# Power-scheme.net
KiCad netlist of a schematic drawn in Altium Designer
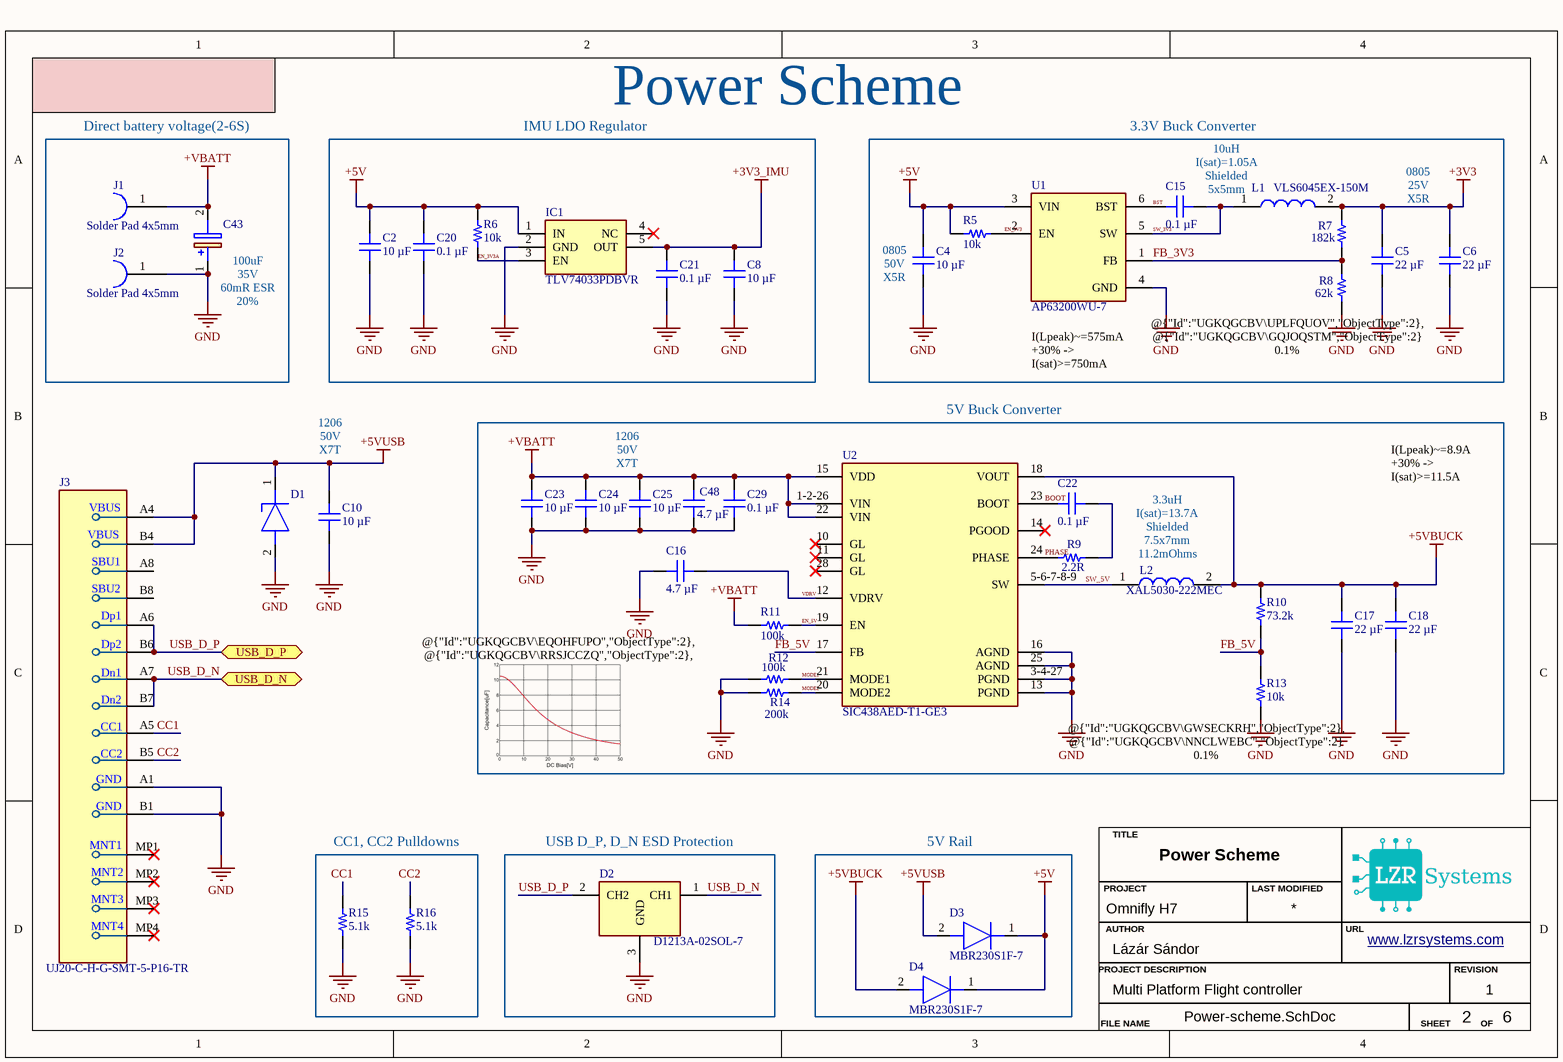
[diagram p0: Power-scheme.SchDoc]

(export (version "E")
  (design (tool "Eeschema 10.0.6"))
  (components
    (comp (ref "C2")
      (value "10 µF")
      (footprint "MURATA GRM21B 0805_2012")
      (description "CAP CER 10UF 50V X5R 0805")
      (fields
        (field (name "PART NUMBER") "GRM21BR61H106ME43L")
        (field (name "CAPACITANCE") "10 µF")
        (field (name "MANUFACTURER") "Murata Electronics")
      )
      (libsource (lib "Celestial Altium Library - altium_library") (part "Capacitor"))
    )
    (comp (ref "C4")
      (value "10 µF")
      (footprint "MURATA GRM21B 0805_2012")
      (description "CAP CER 10UF 50V X5R 0805")
      (fields
        (field (name "PART NUMBER") "GRM21BR61H106ME43L")
        (field (name "CAPACITANCE") "10 µF")
        (field (name "MANUFACTURER") "Murata Electronics")
      )
      (libsource (lib "Celestial Altium Library - altium_library") (part "Capacitor"))
    )
    (comp (ref "C5")
      (value "22 µF")
      (footprint "MURATA GRM21B 0805_2012")
      (description "CAP CER 22UF 16V X5R 0805")
      (fields
        (field (name "PART NUMBER") "GRM21BR61C226ME44L")
        (field (name "CAPACITANCE") "22 µF")
        (field (name "MANUFACTURER") "Murata Electronics")
      )
      (libsource (lib "Celestial Altium Library - altium_library") (part "Capacitor"))
    )
    (comp (ref "C6")
      (value "22 µF")
      (footprint "MURATA GRM21B 0805_2012")
      (description "CAP CER 22UF 16V X5R 0805")
      (fields
        (field (name "PART NUMBER") "GRM21BR61C226ME44L")
        (field (name "CAPACITANCE") "22 µF")
        (field (name "MANUFACTURER") "Murata Electronics")
      )
      (libsource (lib "Celestial Altium Library - altium_library") (part "Capacitor"))
    )
    (comp (ref "C8")
      (value "10 µF")
      (footprint "MURATA GRM21B 0805_2012")
      (description "CAP CER 10UF 50V X5R 0805")
      (fields
        (field (name "PART NUMBER") "GRM21BR61H106ME43L")
        (field (name "CAPACITANCE") "10 µF")
        (field (name "MANUFACTURER") "Murata Electronics")
      )
      (libsource (lib "Celestial Altium Library - altium_library") (part "Capacitor"))
    )
    (comp (ref "C10")
      (value "10 µF")
      (footprint "MURATA GRM21B 0805_2012")
      (description "CAP CER 10UF 50V X5R 0805")
      (fields
        (field (name "PART NUMBER") "GRM21BR61H106ME43L")
        (field (name "CAPACITANCE") "10 µF")
        (field (name "MANUFACTURER") "Murata Electronics")
      )
      (libsource (lib "Celestial Altium Library - altium_library") (part "Capacitor"))
    )
    (comp (ref "C15")
      (value "0.1 µF")
      (footprint "MURATA GCM155 0402_1005")
      (description "CAP CER 0.1UF 50V X7R 0402")
      (fields
        (field (name "PART NUMBER") "GCM155R71H104ME02D")
        (field (name "CAPACITANCE") "0.1 µF")
        (field (name "MANUFACTURER") "Murata Electronics")
      )
      (libsource (lib "Celestial Altium Library - altium_library") (part "Capacitor"))
    )
    (comp (ref "C16")
      (value "4.7 µF")
      (footprint "MURATA GRM21B 0805_2012")
      (description "CAP CER 4.7UF 50V X5R 0805")
      (fields
        (field (name "PART NUMBER") "GRM21BR61H475KE51L")
        (field (name "CAPACITANCE") "4.7 µF")
        (field (name "MANUFACTURER") "Murata Electronics")
      )
      (libsource (lib "Celestial Altium Library - altium_library") (part "Capacitor"))
    )
    (comp (ref "C17")
      (value "22 µF")
      (footprint "CAP 1206_3216 - 0.8MM")
      (description "CAP CER 22UF 16V X6S 1206")
      (fields
        (field (name "PART NUMBER") "GRT31CC81C226ME01L")
        (field (name "CAPACITANCE") "22 µF")
        (field (name "MANUFACTURER") "Murata Electronics")
      )
      (libsource (lib "Celestial Altium Library - altium_library") (part "Capacitor"))
    )
    (comp (ref "C18")
      (value "22 µF")
      (footprint "CAP 1206_3216 - 0.8MM")
      (description "CAP CER 22UF 16V X6S 1206")
      (fields
        (field (name "PART NUMBER") "GRT31CC81C226ME01L")
        (field (name "CAPACITANCE") "22 µF")
        (field (name "MANUFACTURER") "Murata Electronics")
      )
      (libsource (lib "Celestial Altium Library - altium_library") (part "Capacitor"))
    )
    (comp (ref "C20")
      (value "0.1 µF")
      (footprint "MURATA GCM155 0402_1005")
      (description "CAP CER 0.1UF 50V X7R 0402")
      (fields
        (field (name "PART NUMBER") "GCM155R71H104ME02D")
        (field (name "CAPACITANCE") "0.1 µF")
        (field (name "MANUFACTURER") "Murata Electronics")
      )
      (libsource (lib "Celestial Altium Library - altium_library") (part "Capacitor"))
    )
    (comp (ref "C21")
      (value "0.1 µF")
      (footprint "MURATA GCM155 0402_1005")
      (description "CAP CER 0.1UF 50V X7R 0402")
      (fields
        (field (name "PART NUMBER") "GCM155R71H104ME02D")
        (field (name "CAPACITANCE") "0.1 µF")
        (field (name "MANUFACTURER") "Murata Electronics")
      )
      (libsource (lib "Celestial Altium Library - altium_library") (part "Capacitor"))
    )
    (comp (ref "C22")
      (value "0.1 µF")
      (footprint "MURATA GCM155 0402_1005")
      (description "CAP CER 0.1UF 50V X7R 0402")
      (fields
        (field (name "PART NUMBER") "GCM155R71H104ME02D")
        (field (name "CAPACITANCE") "0.1 µF")
        (field (name "MANUFACTURER") "Murata Electronics")
      )
      (libsource (lib "Celestial Altium Library - altium_library") (part "Capacitor"))
    )
    (comp (ref "C23")
      (value "10 µF")
      (footprint "CAP 1206_3216 - 0.8MM")
      (description "CAP CER 10UF 50V X5R 1206")
      (fields
        (field (name "PART NUMBER") "CGA5L3X5R1H106K160AB")
        (field (name "CAPACITANCE") "10 µF")
        (field (name "MANUFACTURER") "TDK Corporation")
      )
      (libsource (lib "Celestial Altium Library - altium_library") (part "Capacitor"))
    )
    (comp (ref "C24")
      (value "10 µF")
      (footprint "CAP 1206_3216 - 0.8MM")
      (description "CAP CER 10UF 50V X5R 1206")
      (fields
        (field (name "PART NUMBER") "CGA5L3X5R1H106K160AB")
        (field (name "CAPACITANCE") "10 µF")
        (field (name "MANUFACTURER") "TDK Corporation")
      )
      (libsource (lib "Celestial Altium Library - altium_library") (part "Capacitor"))
    )
    (comp (ref "C25")
      (value "10 µF")
      (footprint "CAP 1206_3216 - 0.8MM")
      (description "CAP CER 10UF 50V X5R 1206")
      (fields
        (field (name "PART NUMBER") "CGA5L3X5R1H106K160AB")
        (field (name "CAPACITANCE") "10 µF")
        (field (name "MANUFACTURER") "TDK Corporation")
      )
      (libsource (lib "Celestial Altium Library - altium_library") (part "Capacitor"))
    )
    (comp (ref "C29")
      (value "0.1 µF")
      (footprint "MURATA GCM155 0402_1005")
      (description "CAP CER 0.1UF 50V X7R 0402")
      (fields
        (field (name "PART NUMBER") "GCM155R71H104ME02D")
        (field (name "CAPACITANCE") "0.1 µF")
        (field (name "MANUFACTURER") "Murata Electronics")
      )
      (libsource (lib "Celestial Altium Library - altium_library") (part "Capacitor"))
    )
    (comp (ref "C43")
      (value "T523H107M035APE070")
      (footprint "SamacSys:CAPPM7360X200N")
      (description "Capacitor Polarised")
      (fields (field (name "MOUSER PART NUMBER") "80-T523H107M35APE070"))
      (libsource (lib "*") (part "T523H107M035APE070"))
    )
    (comp (ref "C48")
      (value "4.7 µF")
      (footprint "MURATA GRM21B 0805_2012")
      (description "CAP CER 4.7UF 50V X5R 0805")
      (fields
        (field (name "PART NUMBER") "GRM21BR61H475KE51L")
        (field (name "CAPACITANCE") "4.7 µF")
        (field (name "MANUFACTURER") "Murata Electronics")
      )
      (libsource (lib "Celestial Altium Library - altium_library") (part "Capacitor"))
    )
    (comp (ref "D1")
      (value "PESD24VS1UA")
      (footprint "SamacSys:SOD2512X110N")
      (description "Diode ESD (Uni-directional)")
      (fields
        (field (name "MANUFACTURER_PART_NUMBER") "PESD24VS1UA,115")
        (field (name "MOUSER PART NUMBER") "771-PESD24VS1UA115")
      )
      (libsource (lib "*") (part "PESD24VS1UA,115"))
    )
    (comp (ref "D2")
      (value "D1213A-02SOL-7")
      (footprint "SamacSys:D1213A02SOL7")
      (description "TVS Diode (Uni-directional)")
      (fields (field (name "MOUSER PART NUMBER") "621-D1213A-02SOL-7"))
      (libsource (lib "SamacSys") (part "D1213A-02SOL-7"))
    )
    (comp (ref "D3")
      (value "MBR230S1F-7")
      (footprint "SamacSys:SODFL3518X115N")
      (description "Diode")
      (fields (field (name "MOUSER PART NUMBER") "621-MBR230S1F-7"))
      (libsource (lib "*") (part "MBR230S1F-7"))
    )
    (comp (ref "D4")
      (value "MBR230S1F-7")
      (footprint "SamacSys:SODFL3518X115N")
      (description "Diode")
      (fields (field (name "MOUSER PART NUMBER") "621-MBR230S1F-7"))
      (libsource (lib "*") (part "MBR230S1F-7"))
    )
    (comp (ref "IC1")
      (value "TLV74033PDBVR")
      (footprint "SamacSys:SOT95P280X145-5N")
      (description "Integrated Circuit")
      (fields (field (name "MOUSER PART NUMBER") "595-TLV74033PDBVR"))
      (libsource (lib "*") (part "TLV74033PDBVR"))
    )
    (comp (ref "J1")
      (value "Solder Pad 4x5mm")
      (footprint "Solder Pad 4x5mm-Footprint-1")
      (description "Solerd Pad 4x5mm mainly for Flight Controller Vbatt")
      (libsource (lib "Sandor Lazar") (part "Solder Pad 4x5mm"))
    )
    (comp (ref "J2")
      (value "Solder Pad 4x5mm")
      (footprint "Solder Pad 4x5mm-Footprint-1")
      (description "Solerd Pad 4x5mm mainly for Flight Controller Vbatt")
      (libsource (lib "Sandor Lazar") (part "Solder Pad 4x5mm"))
    )
    (comp (ref "J3")
      (value "UJ20-C-H-G-SMT-5-P16-TR")
      (footprint "SamacSys:UJ20CHGSMT5P16TR")
      (description "Connector")
      (fields (field (name "MOUSER PART NUMBER") "179-UJ20CHGSMT5P16TR"))
      (libsource (lib "SamacSys") (part "UJ20-C-H-G-SMT-5-P16-TR"))
    )
    (comp (ref "L1")
      (value "VLS6045EX-150M")
      (footprint "SamacSys:VLS6045")
      (description "Inductor")
      (fields (field (name "MOUSER PART NUMBER") "810-VLS6045EX-150M"))
      (libsource (lib "SamacSys") (part "VLS6045EX-150M"))
    )
    (comp (ref "L2")
      (value "XAL5030-222MEC")
      (footprint "SamacSys:XAL5030222MEC")
      (description "Inductor")
      (fields (field (name "MOUSER PART NUMBER") "994-XAL5030-222MEC"))
      (libsource (lib "*") (part "XAL5030-222MEC"))
    )
    (comp (ref "R5")
      (value "10k")
      (footprint "YAGEO RES 0402_1005")
      (description "RES 10K OHM 0.5% 1/16W 0402")
      (fields (field (name "PART NUMBER") "AC0402DR-0710KL") (field (name "MANUFACTURER") "Yageo"))
      (libsource (lib "Celestial Altium Library - altium_library") (part "Resistor"))
    )
    (comp (ref "R6")
      (value "10k")
      (footprint "YAGEO RES 0402_1005")
      (description "RES 10K OHM 0.5% 1/16W 0402")
      (fields (field (name "PART NUMBER") "AC0402DR-0710KL") (field (name "MANUFACTURER") "Yageo"))
      (libsource (lib "Celestial Altium Library - altium_library") (part "Resistor"))
    )
    (comp (ref "R7")
      (value "182k")
      (footprint "YAGEO RES 0402_1005")
      (description "RES SMD 182K OHM 1% 1/16W 0402")
      (fields (field (name "PART NUMBER") "AC0402FR-07182KL") (field (name "MANUFACTURER") "Yageo"))
      (libsource (lib "Celestial Altium Library - altium_library") (part "Resistor"))
    )
    (comp (ref "R8")
      (value "62k")
      (footprint "YAGEO RES 0402_1005")
      (description "RES SMD 62K OHM 1% 1/16W 0402")
      (fields (field (name "PART NUMBER") "AC0402FR-0762KL") (field (name "MANUFACTURER") "Yageo"))
      (libsource (lib "Celestial Altium Library - altium_library") (part "Resistor"))
    )
    (comp (ref "R9")
      (value "2.2R")
      (footprint "YAGEO RES 0402_1005")
      (description "RES SMD 2.2 OHM 1% 1/16W 0402")
      (fields (field (name "PART NUMBER") "AC0402FR-072R2L") (field (name "MANUFACTURER") "Yageo"))
      (libsource (lib "Celestial Altium Library - altium_library") (part "Resistor"))
    )
    (comp (ref "R10")
      (value "73.2k")
      (footprint "YAGEO RES 0402_1005")
      (description "RES SMD 73.2K OHM 1% 1/16W 0402")
      (fields (field (name "PART NUMBER") "AC0402FR-0773K2L") (field (name "MANUFACTURER") "Yageo"))
      (libsource (lib "Celestial Altium Library - altium_library") (part "Resistor"))
    )
    (comp (ref "R11")
      (value "100k")
      (footprint "YAGEO RES 0402_1005")
      (description "RES SMD 100K OHM 5% 1/16W 0402")
      (fields (field (name "PART NUMBER") "AC0402JR-07100KL") (field (name "MANUFACTURER") "Yageo"))
      (libsource (lib "Celestial Altium Library - altium_library") (part "Resistor"))
    )
    (comp (ref "R12")
      (value "100k")
      (footprint "YAGEO RES 0402_1005")
      (description "RES SMD 100K OHM 5% 1/16W 0402")
      (fields (field (name "PART NUMBER") "AC0402JR-07100KL") (field (name "MANUFACTURER") "Yageo"))
      (libsource (lib "Celestial Altium Library - altium_library") (part "Resistor"))
    )
    (comp (ref "R13")
      (value "10k")
      (footprint "YAGEO RES 0402_1005")
      (description "RES 10K OHM 0.5% 1/16W 0402")
      (fields (field (name "PART NUMBER") "AC0402DR-0710KL") (field (name "MANUFACTURER") "Yageo"))
      (libsource (lib "Celestial Altium Library - altium_library") (part "Resistor"))
    )
    (comp (ref "R14")
      (value "200k")
      (footprint "YAGEO RES 0402_1005")
      (description "RES SMD 200K OHM 5% 1/16W 0402")
      (fields (field (name "PART NUMBER") "AC0402JR-07200KL") (field (name "MANUFACTURER") "Yageo"))
      (libsource (lib "Celestial Altium Library - altium_library") (part "Resistor"))
    )
    (comp (ref "R15")
      (value "5.1k")
      (footprint "YAGEO RES 0402_1005")
      (description "RES SMD 5.1K OHM 5% 1/16W 0402")
      (fields (field (name "PART NUMBER") "AC0402JR-075K1L") (field (name "MANUFACTURER") "Yageo"))
      (libsource (lib "Celestial Altium Library - altium_library") (part "Resistor"))
    )
    (comp (ref "R16")
      (value "5.1k")
      (footprint "YAGEO RES 0402_1005")
      (description "RES SMD 5.1K OHM 5% 1/16W 0402")
      (fields (field (name "PART NUMBER") "AC0402JR-075K1L") (field (name "MANUFACTURER") "Yageo"))
      (libsource (lib "Celestial Altium Library - altium_library") (part "Resistor"))
    )
    (comp (ref "U1")
      (value "AP63200WU-7")
      (footprint "FP-TSOT26-MFG")
      (description "Switching Regulator")
      (libsource (lib "Sandor Lazar") (part "2ae3aed49e7ee94ca813948749813a1"))
    )
    (comp (ref "U2")
      (value "SIC438AED-T1-GE3")
      (footprint "FP-T22-0442-MFG")
      (description "Synchronous Buck Regulator Ultrasonic 28V I/P Adjustable O/P 8A 24-Pin PowerPAK MLP44 T/R")
      (libsource (lib "Sandor Lazar") (part "248a2e7ecd792f7d97452f0be2fd14c"))
    )
  )
  (nets
    (net (code "1") (name "+3V3") (class "Default")
      (node (ref "C5") (pin "2") (pinfunction "2_2") (pintype "passive"))
      (node (ref "C6") (pin "2") (pinfunction "2_2") (pintype "passive"))
      (node (ref "L1") (pin "2") (pinfunction "2_2") (pintype "passive"))
      (node (ref "R7") (pin "2") (pinfunction "2_2") (pintype "passive"))
    )
    (net (code "2") (name "+3V3_IMU") (class "Default")
      (node (ref "C21") (pin "2") (pinfunction "2_2") (pintype "passive"))
      (node (ref "C8") (pin "2") (pinfunction "2_2") (pintype "passive"))
      (node (ref "IC1") (pin "5") (pinfunction "OUT_5") (pintype "passive"))
    )
    (net (code "3") (name "+5V") (class "Default")
      (node (ref "C2") (pin "2") (pinfunction "2_2") (pintype "passive"))
      (node (ref "C20") (pin "2") (pinfunction "2_2") (pintype "passive"))
      (node (ref "C4") (pin "2") (pinfunction "2_2") (pintype "passive"))
      (node (ref "D3") (pin "1") (pinfunction "K_1") (pintype "passive"))
      (node (ref "D4") (pin "1") (pinfunction "K_1") (pintype "passive"))
      (node (ref "IC1") (pin "1") (pinfunction "IN_1") (pintype "passive"))
      (node (ref "R5") (pin "2") (pinfunction "2_2") (pintype "passive"))
      (node (ref "R6") (pin "2") (pinfunction "2_2") (pintype "passive"))
      (node (ref "U1") (pin "3") (pinfunction "VIN_3") (pintype "power_in"))
    )
    (net (code "4") (name "+5VBUCK") (class "Default")
      (node (ref "C17") (pin "2") (pinfunction "2_2") (pintype "passive"))
      (node (ref "C18") (pin "2") (pinfunction "2_2") (pintype "passive"))
      (node (ref "D4") (pin "2") (pinfunction "A_2") (pintype "passive"))
      (node (ref "L2") (pin "2") (pinfunction "2_2") (pintype "passive"))
      (node (ref "R10") (pin "2") (pinfunction "2_2") (pintype "passive"))
      (node (ref "U2") (pin "18") (pinfunction "VOUT_18") (pintype "passive"))
    )
    (net (code "5") (name "+5VUSB") (class "Default")
      (node (ref "C10") (pin "2") (pinfunction "2_2") (pintype "passive"))
      (node (ref "D1") (pin "1") (pinfunction "K_1") (pintype "passive"))
      (node (ref "D3") (pin "2") (pinfunction "A_2") (pintype "passive"))
      (node (ref "J3") (pin "A4") (pinfunction "VBUS_A4") (pintype "passive"))
      (node (ref "J3") (pin "B4") (pinfunction "VBUS_2_B4") (pintype "passive"))
    )
    (net (code "6") (name "+VBATT") (class "Default")
      (node (ref "C23") (pin "2") (pinfunction "2_2") (pintype "passive"))
      (node (ref "C24") (pin "2") (pinfunction "2_2") (pintype "passive"))
      (node (ref "C25") (pin "2") (pinfunction "2_2") (pintype "passive"))
      (node (ref "C29") (pin "2") (pinfunction "2_2") (pintype "passive"))
      (node (ref "C43") (pin "2") (pinfunction "-_2") (pintype "passive"))
      (node (ref "C48") (pin "2") (pinfunction "2_2") (pintype "passive"))
      (node (ref "J1") (pin "1") (pinfunction "*_1") (pintype "power_in"))
      (node (ref "R11") (pin "1") (pinfunction "1_1") (pintype "passive"))
      (node (ref "U2") (pin "1-2-26") (pinfunction "VIN_1-2-26") (pintype "power_in"))
      (node (ref "U2") (pin "15") (pinfunction "VDD_15") (pintype "power_in"))
      (node (ref "U2") (pin "22") (pinfunction "VIN_22") (pintype "power_in"))
    )
    (net (code "7") (name "/BOOT") (class "Default")
      (node (ref "C22") (pin "2") (pinfunction "2_2") (pintype "passive"))
      (node (ref "U2") (pin "23") (pinfunction "BOOT_23") (pintype "passive"))
    )
    (net (code "8") (name "/BST") (class "Default")
      (node (ref "C15") (pin "2") (pinfunction "2_2") (pintype "passive"))
      (node (ref "U1") (pin "6") (pinfunction "BST_6") (pintype "passive"))
    )
    (net (code "9") (name "/CC1") (class "Default")
      (node (ref "J3") (pin "A5") (pinfunction "CC1_A5") (pintype "passive"))
      (node (ref "R15") (pin "2") (pinfunction "2_2") (pintype "passive"))
    )
    (net (code "10") (name "/CC2") (class "Default")
      (node (ref "J3") (pin "B5") (pinfunction "CC2_B5") (pintype "passive"))
      (node (ref "R16") (pin "2") (pinfunction "2_2") (pintype "passive"))
    )
    (net (code "11") (name "/EN_3V3") (class "Default")
      (node (ref "R5") (pin "1") (pinfunction "1_1") (pintype "passive"))
      (node (ref "U1") (pin "2") (pinfunction "EN_2") (pintype "passive"))
    )
    (net (code "12") (name "/EN_3V3A") (class "Default")
      (node (ref "IC1") (pin "3") (pinfunction "EN_3") (pintype "passive"))
      (node (ref "R6") (pin "1") (pinfunction "1_1") (pintype "passive"))
    )
    (net (code "13") (name "/EN_5V") (class "Default")
      (node (ref "R11") (pin "2") (pinfunction "2_2") (pintype "passive"))
      (node (ref "U2") (pin "19") (pinfunction "EN_19") (pintype "passive"))
    )
    (net (code "14") (name "/FB_3V3") (class "Default")
      (node (ref "R7") (pin "1") (pinfunction "1_1") (pintype "passive"))
      (node (ref "R8") (pin "1") (pinfunction "1_1") (pintype "passive"))
      (node (ref "U1") (pin "1") (pinfunction "FB_1") (pintype "passive"))
    )
    (net (code "15") (name "/FB_5V") (class "Default")
      (node (ref "R10") (pin "1") (pinfunction "1_1") (pintype "passive"))
      (node (ref "R13") (pin "1") (pinfunction "1_1") (pintype "passive"))
      (node (ref "U2") (pin "17") (pinfunction "FB_17") (pintype "passive"))
    )
    (net (code "16") (name "/MODE1") (class "Default")
      (node (ref "R12") (pin "2") (pinfunction "2_2") (pintype "passive"))
      (node (ref "U2") (pin "21") (pinfunction "MODE1_21") (pintype "passive"))
    )
    (net (code "17") (name "/MODE2") (class "Default")
      (node (ref "R14") (pin "2") (pinfunction "2_2") (pintype "passive"))
      (node (ref "U2") (pin "20") (pinfunction "MODE2_20") (pintype "passive"))
    )
    (net (code "18") (name "/PHASE") (class "Default")
      (node (ref "R9") (pin "1") (pinfunction "1_1") (pintype "passive"))
      (node (ref "U2") (pin "24") (pinfunction "PHASE_24") (pintype "passive"))
    )
    (net (code "19") (name "/SW_3V3") (class "Default")
      (node (ref "C15") (pin "1") (pinfunction "1_1") (pintype "passive"))
      (node (ref "L1") (pin "1") (pinfunction "1_1") (pintype "passive"))
      (node (ref "U1") (pin "5") (pinfunction "SW_5") (pintype "passive"))
    )
    (net (code "20") (name "/SW_5V") (class "Default")
      (node (ref "L2") (pin "1") (pinfunction "1_1") (pintype "passive"))
      (node (ref "U2") (pin "5-6-7-8-9") (pinfunction "SW_5-6-7-8-9") (pintype "passive"))
    )
    (net (code "21") (name "/USB_D_N") (class "Default")
      (node (ref "D2") (pin "1") (pinfunction "CH1_1") (pintype "passive"))
      (node (ref "J3") (pin "A7") (pinfunction "DN1_A7") (pintype "passive"))
      (node (ref "J3") (pin "B7") (pinfunction "DN2_B7") (pintype "passive"))
    )
    (net (code "22") (name "/USB_D_P") (class "Default")
      (node (ref "D2") (pin "2") (pinfunction "CH2_2") (pintype "passive"))
      (node (ref "J3") (pin "A6") (pinfunction "DP1_A6") (pintype "passive"))
      (node (ref "J3") (pin "B6") (pinfunction "DP2_B6") (pintype "passive"))
    )
    (net (code "23") (name "/VDRV") (class "Default")
      (node (ref "C16") (pin "2") (pinfunction "2_2") (pintype "passive"))
      (node (ref "U2") (pin "12") (pinfunction "VDRV_12") (pintype "power_in"))
    )
    (net (code "24") (name "GND") (class "Default")
      (node (ref "C10") (pin "1") (pinfunction "1_1") (pintype "passive"))
      (node (ref "C16") (pin "1") (pinfunction "1_1") (pintype "passive"))
      (node (ref "C17") (pin "1") (pinfunction "1_1") (pintype "passive"))
      (node (ref "C18") (pin "1") (pinfunction "1_1") (pintype "passive"))
      (node (ref "C2") (pin "1") (pinfunction "1_1") (pintype "passive"))
      (node (ref "C20") (pin "1") (pinfunction "1_1") (pintype "passive"))
      (node (ref "C21") (pin "1") (pinfunction "1_1") (pintype "passive"))
      (node (ref "C23") (pin "1") (pinfunction "1_1") (pintype "passive"))
      (node (ref "C24") (pin "1") (pinfunction "1_1") (pintype "passive"))
      (node (ref "C25") (pin "1") (pinfunction "1_1") (pintype "passive"))
      (node (ref "C29") (pin "1") (pinfunction "1_1") (pintype "passive"))
      (node (ref "C4") (pin "1") (pinfunction "1_1") (pintype "passive"))
      (node (ref "C43") (pin "1") (pinfunction "+_1") (pintype "passive"))
      (node (ref "C48") (pin "1") (pinfunction "1_1") (pintype "passive"))
      (node (ref "C5") (pin "1") (pinfunction "1_1") (pintype "passive"))
      (node (ref "C6") (pin "1") (pinfunction "1_1") (pintype "passive"))
      (node (ref "C8") (pin "1") (pinfunction "1_1") (pintype "passive"))
      (node (ref "D1") (pin "2") (pinfunction "A_2") (pintype "passive"))
      (node (ref "D2") (pin "3") (pinfunction "GND_3") (pintype "passive"))
      (node (ref "IC1") (pin "2") (pinfunction "GND_2") (pintype "passive"))
      (node (ref "J2") (pin "1") (pinfunction "*_1") (pintype "power_in"))
      (node (ref "J3") (pin "A1") (pinfunction "GND_1_A1") (pintype "passive"))
      (node (ref "J3") (pin "B1") (pinfunction "GND_2_B1") (pintype "passive"))
      (node (ref "R12") (pin "1") (pinfunction "1_1") (pintype "passive"))
      (node (ref "R13") (pin "2") (pinfunction "2_2") (pintype "passive"))
      (node (ref "R14") (pin "1") (pinfunction "1_1") (pintype "passive"))
      (node (ref "R15") (pin "1") (pinfunction "1_1") (pintype "passive"))
      (node (ref "R16") (pin "1") (pinfunction "1_1") (pintype "passive"))
      (node (ref "R8") (pin "2") (pinfunction "2_2") (pintype "passive"))
      (node (ref "U1") (pin "4") (pinfunction "GND_4") (pintype "power_in"))
      (node (ref "U2") (pin "13") (pinfunction "PGND_13") (pintype "power_in"))
      (node (ref "U2") (pin "16") (pinfunction "AGND_16") (pintype "power_in"))
      (node (ref "U2") (pin "25") (pinfunction "AGND_25") (pintype "power_in"))
      (node (ref "U2") (pin "3-4-27") (pinfunction "PGND_3-4-27") (pintype "power_in"))
    )
    (net (code "25") (name "Net-(C22-Pad1)") (class "Default")
      (node (ref "C22") (pin "1") (pinfunction "1_1") (pintype "passive"))
      (node (ref "R9") (pin "2") (pinfunction "2_2") (pintype "passive"))
    )
    (net (code "26") (name "unconnected-(IC1-NC-Pad4)") (class "Default")
      (node (ref "IC1") (pin "4") (pinfunction "NC_4") (pintype "passive+no_connect"))
    )
    (net (code "27") (name "unconnected-(J3-PadMP1)") (class "Default")
      (node (ref "J3") (pin "MP1") (pinfunction "MP1_MP1") (pintype "passive+no_connect"))
    )
    (net (code "28") (name "unconnected-(J3-PadMP2)") (class "Default")
      (node (ref "J3") (pin "MP2") (pinfunction "MP2_MP2") (pintype "passive+no_connect"))
    )
    (net (code "29") (name "unconnected-(J3-PadMP3)") (class "Default")
      (node (ref "J3") (pin "MP3") (pinfunction "MP3_MP3") (pintype "passive+no_connect"))
    )
    (net (code "30") (name "unconnected-(J3-PadMP4)") (class "Default")
      (node (ref "J3") (pin "MP4") (pinfunction "MP4_MP4") (pintype "passive+no_connect"))
    )
    (net (code "31") (name "unconnected-(J3-SBU1-PadA8)") (class "Default")
      (node (ref "J3") (pin "A8") (pinfunction "SBU1_A8") (pintype "passive"))
    )
    (net (code "32") (name "unconnected-(J3-SBU2-PadB8)") (class "Default")
      (node (ref "J3") (pin "B8") (pinfunction "SBU2_B8") (pintype "passive"))
    )
    (net (code "33") (name "unconnected-(U2-GL-Pad10)") (class "Default")
      (node (ref "U2") (pin "10") (pinfunction "GL_10") (pintype "passive+no_connect"))
    )
    (net (code "34") (name "unconnected-(U2-GL-Pad11)") (class "Default")
      (node (ref "U2") (pin "11") (pinfunction "GL_11") (pintype "passive+no_connect"))
    )
    (net (code "35") (name "unconnected-(U2-GL-Pad28)") (class "Default")
      (node (ref "U2") (pin "28") (pinfunction "GL_28") (pintype "passive+no_connect"))
    )
    (net (code "36") (name "unconnected-(U2-PGOOD-Pad14)") (class "Default")
      (node (ref "U2") (pin "14") (pinfunction "PGOOD_14") (pintype "open_collector+no_connect"))
    )
  )
)
